# MINI_SAM_D51_010.net
KiCad netlist of a schematic drawn in EAGLE
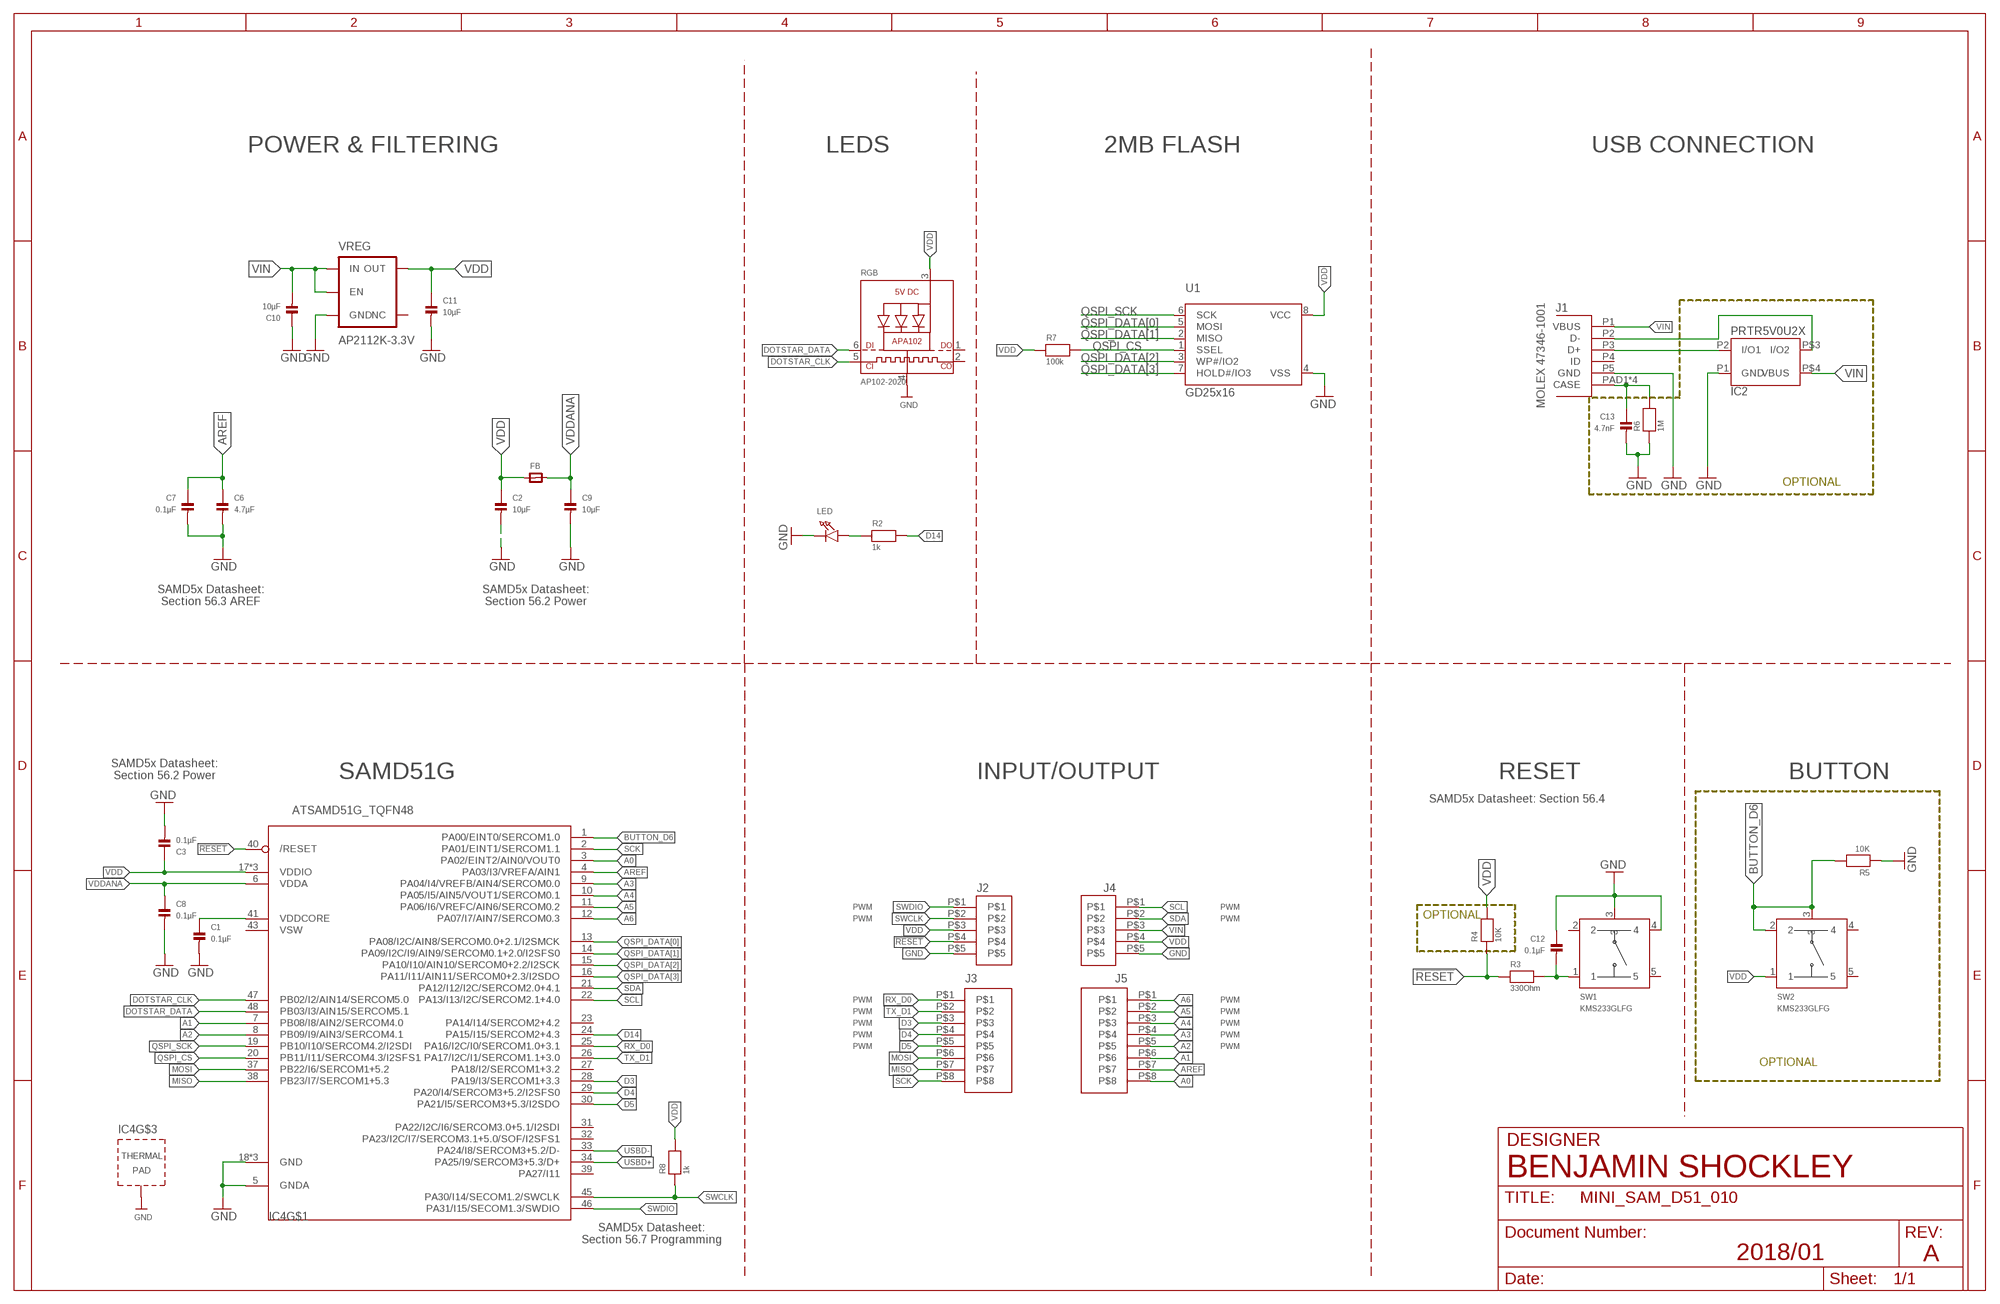
[diagram p0: schematic, sheet 1]

(export (version "E")
  (design (tool "Eeschema 10.0.6"))
  (components
    (comp (ref "C1")
      (value "0.1µF")
      (footprint "eagle-import:_0603MP")
      (libsource (lib "eagle-import") (part "CAP_CERAMIC_0603MP"))
    )
    (comp (ref "C2")
      (value "10µF")
      (footprint "eagle-import:_0603MP")
      (libsource (lib "eagle-import") (part "CAP_CERAMIC_0603MP"))
    )
    (comp (ref "C3")
      (value "0.1µF")
      (footprint "eagle-import:_0603MP")
      (libsource (lib "eagle-import") (part "CAP_CERAMIC_0603MP"))
    )
    (comp (ref "C6")
      (value "4.7µF")
      (footprint "eagle-import:_0603MP")
      (libsource (lib "eagle-import") (part "CAP_CERAMIC_0603MP"))
    )
    (comp (ref "C7")
      (value "0.1µF")
      (footprint "eagle-import:_0603MP")
      (libsource (lib "eagle-import") (part "CAP_CERAMIC_0603MP"))
    )
    (comp (ref "C8")
      (value "0.1µF")
      (footprint "eagle-import:_0603MP")
      (libsource (lib "eagle-import") (part "CAP_CERAMIC_0603MP"))
    )
    (comp (ref "C9")
      (value "10µF")
      (footprint "eagle-import:_0603MP")
      (libsource (lib "eagle-import") (part "CAP_CERAMIC_0603MP"))
    )
    (comp (ref "C10")
      (value "10µF")
      (footprint "eagle-import:_0603MP")
      (libsource (lib "eagle-import") (part "CAP_CERAMIC_0603MP"))
    )
    (comp (ref "C11")
      (value "10µF")
      (footprint "eagle-import:_0603MP")
      (libsource (lib "eagle-import") (part "CAP_CERAMIC_0603MP"))
    )
    (comp (ref "C12")
      (value "0.1µF")
      (footprint "eagle-import:_0603MP")
      (libsource (lib "eagle-import") (part "CAP_CERAMIC_0603MP"))
    )
    (comp (ref "C13")
      (value "4.7nF")
      (footprint "eagle-import:_0603MP")
      (libsource (lib "eagle-import") (part "CAP_CERAMIC_0603MP"))
    )
    (comp (ref "FB")
      (value "FERRITE_0603MP")
      (footprint "eagle-import:_0603MP")
      (libsource (lib "eagle-import") (part "FERRITE_0603MP"))
    )
    (comp (ref "IC2")
      (value "PRTR5V0U2X")
      (footprint "eagle-import:SOT143B_REFLOW")
      (libsource (lib "eagle-import") (part "PRTR5V0U2X"))
    )
    (comp (ref "IC4")
      (value "ATSAMD51G_TQFN48")
      (footprint "eagle-import:TQFN48_7MM")
      (libsource (lib "eagle-import") (part "ATSAMD51G_TQFN48"))
    )
    (comp (ref "J1")
      (value "MOLEX_47346-100147346")
      (footprint "eagle-import:MOLEX_47346-1001")
      (libsource (lib "eagle-import") (part "MOLEX_47346-100147346"))
    )
    (comp (ref "J2")
      (value "1X5_HEADER_1.27MM")
      (footprint "eagle-import:1X5_HEADER_1.27MM")
      (libsource (lib "eagle-import") (part "1X5_HEADER_1.27MM"))
    )
    (comp (ref "J3")
      (value "1X8_HEADER_1.27MM")
      (footprint "eagle-import:1X8_HEADER_1.27MM")
      (libsource (lib "eagle-import") (part "1X8_HEADER_1.27MM"))
    )
    (comp (ref "J4")
      (value "1X5_HEADER_1.27MM")
      (footprint "eagle-import:1X5_HEADER_1.27MM")
      (libsource (lib "eagle-import") (part "1X5_HEADER_1.27MM"))
    )
    (comp (ref "J5")
      (value "1X8_HEADER_1.27MM")
      (footprint "eagle-import:1X8_HEADER_1.27MM")
      (libsource (lib "eagle-import") (part "1X8_HEADER_1.27MM"))
    )
    (comp (ref "LED")
      (value "LED0805_NOOUTLINE")
      (footprint "eagle-import:CHIPLED_0805_NOOUTLINE")
      (libsource (lib "eagle-import") (part "LED0805_NOOUTLINE"))
    )
    (comp (ref "R2")
      (value "1k")
      (footprint "eagle-import:_0603MP")
      (libsource (lib "eagle-import") (part "RESISTOR_0603MP"))
    )
    (comp (ref "R3")
      (value "330Ohm")
      (footprint "eagle-import:_0603MP")
      (libsource (lib "eagle-import") (part "RESISTOR_0603MP"))
    )
    (comp (ref "R4")
      (value "10K")
      (footprint "eagle-import:_0603MP")
      (libsource (lib "eagle-import") (part "RESISTOR_0603MP"))
    )
    (comp (ref "R5")
      (value "10K")
      (footprint "eagle-import:_0603MP")
      (libsource (lib "eagle-import") (part "RESISTOR_0603MP"))
    )
    (comp (ref "R6")
      (value "1M")
      (footprint "eagle-import:_0603MP")
      (libsource (lib "eagle-import") (part "RESISTOR_0603MP"))
    )
    (comp (ref "R7")
      (value "100k")
      (footprint "eagle-import:_0603MP")
      (libsource (lib "eagle-import") (part "RESISTOR_0603MP"))
    )
    (comp (ref "R8")
      (value "1k")
      (footprint "eagle-import:_0603MP")
      (libsource (lib "eagle-import") (part "RESISTOR_0603MP"))
    )
    (comp (ref "RGB")
      (value "AP102-2020")
      (footprint "eagle-import:APA102_2020")
      (libsource (lib "eagle-import") (part "APA1022020"))
    )
    (comp (ref "SW1")
      (value "KMS233GLFG")
      (footprint "eagle-import:KMS_SWITCH")
      (libsource (lib "eagle-import") (part "KMS_SWITCHKMS"))
    )
    (comp (ref "SW2")
      (value "KMS233GLFG")
      (footprint "eagle-import:KMS_SWITCH")
      (libsource (lib "eagle-import") (part "KMS_SWITCHKMS"))
    )
    (comp (ref "U1")
      (value "GD25x16")
      (footprint "eagle-import:USON8")
      (libsource (lib "eagle-import") (part "SPIFLASH_8PINUX"))
    )
    (comp (ref "VREG")
      (value "AP2112K-3.3V")
      (footprint "eagle-import:SOT23-5")
      (libsource (lib "eagle-import") (part "V_REG_AP2112K-3.3V"))
    )
  )
  (nets
    (net (code "1") (name "/VSW") (class "Default")
      (node (ref "IC4") (pin "43") (pinfunction "VSW_43") (pintype "power_in"))
    )
    (net (code "2") (name "/~{RESET}") (class "Default")
      (node (ref "IC4") (pin "40") (pinfunction "/RESET_40") (pintype "bidirectional"))
      (node (ref "J2") (pin "P$4") (pinfunction "P$4_P$4") (pintype "bidirectional"))
      (node (ref "R3") (pin "1") (pinfunction "1_1") (pintype "passive"))
      (node (ref "R4") (pin "1") (pinfunction "1_1") (pintype "passive"))
    )
    (net (code "3") (name "A0") (class "Default")
      (node (ref "IC4") (pin "3") (pinfunction "PA02/EINT2/AIN0/VOUT0_3") (pintype "bidirectional"))
      (node (ref "J5") (pin "P$8") (pinfunction "P$8_P$8") (pintype "bidirectional"))
    )
    (net (code "4") (name "A1") (class "Default")
      (node (ref "IC4") (pin "7") (pinfunction "PB08/I8/AIN2/SERCOM4.0_7") (pintype "bidirectional"))
      (node (ref "J5") (pin "P$6") (pinfunction "P$6_P$6") (pintype "bidirectional"))
    )
    (net (code "5") (name "A2") (class "Default")
      (node (ref "IC4") (pin "8") (pinfunction "PB09/I9/AIN3/SERCOM4.1_8") (pintype "bidirectional"))
      (node (ref "J5") (pin "P$5") (pinfunction "P$5_P$5") (pintype "bidirectional"))
    )
    (net (code "6") (name "A3") (class "Default")
      (node (ref "IC4") (pin "9") (pinfunction "PA04/I4/VREFB/AIN4/SERCOM0.0_9") (pintype "bidirectional"))
      (node (ref "J5") (pin "P$4") (pinfunction "P$4_P$4") (pintype "bidirectional"))
    )
    (net (code "7") (name "A4") (class "Default")
      (node (ref "IC4") (pin "10") (pinfunction "PA05/I5/AIN5/VOUT1/SERCOM0.1_10") (pintype "bidirectional"))
      (node (ref "J5") (pin "P$3") (pinfunction "P$3_P$3") (pintype "bidirectional"))
    )
    (net (code "8") (name "A5") (class "Default")
      (node (ref "IC4") (pin "11") (pinfunction "PA06/I6/VREFC/AIN6/SERCOM0.2_11") (pintype "bidirectional"))
      (node (ref "J5") (pin "P$2") (pinfunction "P$2_P$2") (pintype "bidirectional"))
    )
    (net (code "9") (name "A6") (class "Default")
      (node (ref "IC4") (pin "12") (pinfunction "PA07/I7/AIN7/SERCOM0.3_12") (pintype "bidirectional"))
      (node (ref "J5") (pin "P$1") (pinfunction "P$1_P$1") (pintype "bidirectional"))
    )
    (net (code "10") (name "AREF") (class "Default")
      (node (ref "C6") (pin "1") (pinfunction "P$1_1") (pintype "passive"))
      (node (ref "C7") (pin "1") (pinfunction "P$1_1") (pintype "passive"))
      (node (ref "IC4") (pin "4") (pinfunction "PA03/I3/VREFA/AIN1_4") (pintype "bidirectional"))
      (node (ref "J5") (pin "P$7") (pinfunction "P$7_P$7") (pintype "bidirectional"))
    )
    (net (code "11") (name "BUTTON_D6") (class "Default")
      (node (ref "IC4") (pin "1") (pinfunction "PA00/EINT0/SERCOM1.0_1") (pintype "bidirectional"))
      (node (ref "R5") (pin "2") (pinfunction "2_2") (pintype "passive"))
      (node (ref "SW2") (pin "2") (pinfunction "2_2") (pintype "bidirectional"))
      (node (ref "SW2") (pin "3") (pinfunction "3_3") (pintype "bidirectional"))
    )
    (net (code "12") (name "D3") (class "Default")
      (node (ref "IC4") (pin "28") (pinfunction "PA19/I3/SERCOM1+3.3_28") (pintype "bidirectional"))
      (node (ref "J3") (pin "P$3") (pinfunction "P$3_P$3") (pintype "bidirectional"))
    )
    (net (code "13") (name "D4") (class "Default")
      (node (ref "IC4") (pin "29") (pinfunction "PA20/I4/SERCOM3+5.2/I2SFS0_29") (pintype "bidirectional"))
      (node (ref "J3") (pin "P$4") (pinfunction "P$4_P$4") (pintype "bidirectional"))
    )
    (net (code "14") (name "D5") (class "Default")
      (node (ref "IC4") (pin "30") (pinfunction "PA21/I5/SERCOM3+5.3/I2SDO_30") (pintype "bidirectional"))
      (node (ref "J3") (pin "P$5") (pinfunction "P$5_P$5") (pintype "bidirectional"))
    )
    (net (code "15") (name "D14") (class "Default")
      (node (ref "IC4") (pin "24") (pinfunction "PA15/I15/SERCOM2+4.3_24") (pintype "bidirectional"))
      (node (ref "R2") (pin "2") (pinfunction "2_2") (pintype "passive"))
    )
    (net (code "16") (name "DOTSTAR_CLK") (class "Default")
      (node (ref "IC4") (pin "47") (pinfunction "PB02/I2/AIN14/SERCOM5.0_47") (pintype "bidirectional"))
      (node (ref "RGB") (pin "5") (pinfunction "CKI_5") (pintype "input"))
    )
    (net (code "17") (name "DOTSTAR_DATA") (class "Default")
      (node (ref "IC4") (pin "48") (pinfunction "PB03/I3/AIN15/SERCOM5.1_48") (pintype "bidirectional"))
      (node (ref "RGB") (pin "6") (pinfunction "DI_6") (pintype "input"))
    )
    (net (code "18") (name "GND") (class "Default")
      (node (ref "C1") (pin "2") (pinfunction "P$2_2") (pintype "passive"))
      (node (ref "C10") (pin "1") (pinfunction "P$1_1") (pintype "passive"))
      (node (ref "C11") (pin "2") (pinfunction "P$2_2") (pintype "passive"))
      (node (ref "C12") (pin "1") (pinfunction "P$1_1") (pintype "passive"))
      (node (ref "C13") (pin "2") (pinfunction "P$2_2") (pintype "passive"))
      (node (ref "C2") (pin "2") (pinfunction "P$2_2") (pintype "passive"))
      (node (ref "C3") (pin "2") (pinfunction "P$2_2") (pintype "passive"))
      (node (ref "C6") (pin "2") (pinfunction "P$2_2") (pintype "passive"))
      (node (ref "C7") (pin "2") (pinfunction "P$2_2") (pintype "passive"))
      (node (ref "C8") (pin "2") (pinfunction "P$2_2") (pintype "passive"))
      (node (ref "C9") (pin "2") (pinfunction "P$2_2") (pintype "passive"))
      (node (ref "IC2") (pin "P1") (pinfunction "GND_P1") (pintype "bidirectional"))
      (node (ref "IC4") (pin "18") (pinfunction "GND_18") (pintype "power_in"))
      (node (ref "IC4") (pin "35") (pinfunction "GND_35") (pintype "power_in"))
      (node (ref "IC4") (pin "42") (pinfunction "GND_42") (pintype "power_in"))
      (node (ref "IC4") (pin "5") (pinfunction "GNDA_5") (pintype "power_in"))
      (node (ref "IC4") (pin "THERMAL") (pinfunction "TP_THERMAL") (pintype "power_in"))
      (node (ref "J1") (pin "P5") (pinfunction "GND_P5") (pintype "power_in"))
      (node (ref "J2") (pin "P$5") (pinfunction "P$5_P$5") (pintype "bidirectional"))
      (node (ref "J4") (pin "P$5") (pinfunction "P$5_P$5") (pintype "bidirectional"))
      (node (ref "LED") (pin "C") (pinfunction "C_C") (pintype "passive"))
      (node (ref "R5") (pin "1") (pinfunction "1_1") (pintype "passive"))
      (node (ref "R6") (pin "1") (pinfunction "1_1") (pintype "passive"))
      (node (ref "RGB") (pin "4") (pinfunction "GND_4") (pintype "power_in"))
      (node (ref "SW1") (pin "3") (pinfunction "3_3") (pintype "bidirectional"))
      (node (ref "SW1") (pin "4") (pinfunction "4_4") (pintype "bidirectional"))
      (node (ref "U1") (pin "4") (pinfunction "VSS_4") (pintype "bidirectional"))
      (node (ref "VREG") (pin "2") (pinfunction "GND_2") (pintype "input"))
    )
    (net (code "19") (name "MISO") (class "Default")
      (node (ref "IC4") (pin "38") (pinfunction "PB23/I7/SERCOM1+5.3_38") (pintype "bidirectional"))
      (node (ref "J3") (pin "P$7") (pinfunction "P$7_P$7") (pintype "bidirectional"))
    )
    (net (code "20") (name "MOSI") (class "Default")
      (node (ref "IC4") (pin "37") (pinfunction "PB22/I6/SERCOM1+5.2_37") (pintype "bidirectional"))
      (node (ref "J3") (pin "P$6") (pinfunction "P$6_P$6") (pintype "bidirectional"))
    )
    (net (code "21") (name "Net-(C1-P$1)") (class "Default")
      (node (ref "C1") (pin "1") (pinfunction "P$1_1") (pintype "passive"))
      (node (ref "IC4") (pin "41") (pinfunction "VDDCORE_41") (pintype "power_in"))
    )
    (net (code "22") (name "Net-(C12-P$2)") (class "Default")
      (node (ref "C12") (pin "2") (pinfunction "P$2_2") (pintype "passive"))
      (node (ref "R3") (pin "2") (pinfunction "2_2") (pintype "passive"))
      (node (ref "SW1") (pin "1") (pinfunction "1_1") (pintype "bidirectional"))
    )
    (net (code "23") (name "Net-(C13-P$1)") (class "Default")
      (node (ref "C13") (pin "1") (pinfunction "P$1_1") (pintype "passive"))
      (node (ref "J1") (pin "PAD1") (pinfunction "CASE_PAD1") (pintype "bidirectional"))
      (node (ref "J1") (pin "PAD2") (pinfunction "CASE_PAD2") (pintype "bidirectional"))
      (node (ref "J1") (pin "PAD3") (pinfunction "CASE_PAD3") (pintype "bidirectional"))
      (node (ref "J1") (pin "PAD4") (pinfunction "CASE_PAD4") (pintype "bidirectional"))
      (node (ref "R6") (pin "2") (pinfunction "2_2") (pintype "passive"))
    )
    (net (code "24") (name "Net-(LED-PadA)") (class "Default")
      (node (ref "LED") (pin "A") (pinfunction "A_A") (pintype "passive"))
      (node (ref "R2") (pin "1") (pinfunction "1_1") (pintype "passive"))
    )
    (net (code "25") (name "QSPI_CS") (class "Default")
      (node (ref "IC4") (pin "20") (pinfunction "PB11/I11/SERCOM4.3/I2SFS1_20") (pintype "bidirectional"))
      (node (ref "R7") (pin "2") (pinfunction "2_2") (pintype "passive"))
      (node (ref "U1") (pin "1") (pinfunction "SSEL_1") (pintype "bidirectional"))
    )
    (net (code "26") (name "QSPI_DATA[0]") (class "Default")
      (node (ref "IC4") (pin "13") (pinfunction "PA08/I2C/AIN8/SERCOM0.0+2.1/I2SMCK_13") (pintype "bidirectional"))
      (node (ref "U1") (pin "5") (pinfunction "MOSI_5") (pintype "bidirectional"))
    )
    (net (code "27") (name "QSPI_DATA[1]") (class "Default")
      (node (ref "IC4") (pin "14") (pinfunction "PA09/I2C/I9/AIN9/SERCOM0.1+2.0/I2SFS0_14") (pintype "bidirectional"))
      (node (ref "U1") (pin "2") (pinfunction "MISO_2") (pintype "bidirectional"))
    )
    (net (code "28") (name "QSPI_DATA[2]") (class "Default")
      (node (ref "IC4") (pin "15") (pinfunction "PA10/I10/AIN10/SERCOM0+2.2/I2SCK_15") (pintype "bidirectional"))
      (node (ref "U1") (pin "3") (pinfunction "WP#/IO2_3") (pintype "bidirectional"))
    )
    (net (code "29") (name "QSPI_DATA[3]") (class "Default")
      (node (ref "IC4") (pin "16") (pinfunction "PA11/I11/AIN11/SERCOM0+2.3/I2SDO_16") (pintype "bidirectional"))
      (node (ref "U1") (pin "7") (pinfunction "HOLD#/IO3_7") (pintype "bidirectional"))
    )
    (net (code "30") (name "QSPI_SCK") (class "Default")
      (node (ref "IC4") (pin "19") (pinfunction "PB10/I10/SERCOM4.2/I2SDI_19") (pintype "bidirectional"))
      (node (ref "U1") (pin "6") (pinfunction "SCK_6") (pintype "bidirectional"))
    )
    (net (code "31") (name "RX_D0") (class "Default")
      (node (ref "IC4") (pin "25") (pinfunction "PA16/I2C/I0/SERCOM1.0+3.1_25") (pintype "bidirectional"))
      (node (ref "J3") (pin "P$1") (pinfunction "P$1_P$1") (pintype "bidirectional"))
    )
    (net (code "32") (name "SCK") (class "Default")
      (node (ref "IC4") (pin "2") (pinfunction "PA01/EINT1/SERCOM1.1_2") (pintype "bidirectional"))
      (node (ref "J3") (pin "P$8") (pinfunction "P$8_P$8") (pintype "bidirectional"))
    )
    (net (code "33") (name "SCL") (class "Default")
      (node (ref "IC4") (pin "22") (pinfunction "PA13/I13/I2C/SERCOM2.1+4.0_22") (pintype "bidirectional"))
      (node (ref "J4") (pin "P$1") (pinfunction "P$1_P$1") (pintype "bidirectional"))
    )
    (net (code "34") (name "SDA") (class "Default")
      (node (ref "IC4") (pin "21") (pinfunction "PA12/I12/I2C/SERCOM2.0+4.1_21") (pintype "bidirectional"))
      (node (ref "J4") (pin "P$2") (pinfunction "P$2_P$2") (pintype "bidirectional"))
    )
    (net (code "35") (name "SWCLK") (class "Default")
      (node (ref "IC4") (pin "45") (pinfunction "PA30/I14/SECOM1.2/SWCLK_45") (pintype "bidirectional"))
      (node (ref "J2") (pin "P$2") (pinfunction "P$2_P$2") (pintype "bidirectional"))
      (node (ref "R8") (pin "1") (pinfunction "1_1") (pintype "passive"))
    )
    (net (code "36") (name "SWDIO") (class "Default")
      (node (ref "IC4") (pin "46") (pinfunction "PA31/I15/SECOM1.3/SWDIO_46") (pintype "bidirectional"))
      (node (ref "J2") (pin "P$1") (pinfunction "P$1_P$1") (pintype "bidirectional"))
    )
    (net (code "37") (name "TX_D1") (class "Default")
      (node (ref "IC4") (pin "26") (pinfunction "PA17/I2C/I1/SERCOM1.1+3.0_26") (pintype "bidirectional"))
      (node (ref "J3") (pin "P$2") (pinfunction "P$2_P$2") (pintype "bidirectional"))
    )
    (net (code "38") (name "USBD+") (class "Default")
      (node (ref "IC2") (pin "P2") (pinfunction "I/O1_P2") (pintype "bidirectional"))
      (node (ref "IC4") (pin "34") (pinfunction "PA25/I9/SERCOM3+5.3/D+_34") (pintype "bidirectional"))
      (node (ref "J1") (pin "P3") (pinfunction "D+_P3") (pintype "bidirectional"))
    )
    (net (code "39") (name "USBD-") (class "Default")
      (node (ref "IC2") (pin "P$3") (pinfunction "I/O2_P$3") (pintype "bidirectional"))
      (node (ref "IC4") (pin "33") (pinfunction "PA24/I8/SERCOM3+5.2/D-_33") (pintype "bidirectional"))
      (node (ref "J1") (pin "P2") (pinfunction "D-_P2") (pintype "bidirectional"))
    )
    (net (code "40") (name "VDD") (class "Default")
      (node (ref "C11") (pin "1") (pinfunction "P$1_1") (pintype "passive"))
      (node (ref "C2") (pin "1") (pinfunction "P$1_1") (pintype "passive"))
      (node (ref "C3") (pin "1") (pinfunction "P$1_1") (pintype "passive"))
      (node (ref "FB") (pin "1") (pinfunction "P$1_1") (pintype "passive"))
      (node (ref "IC4") (pin "17") (pinfunction "VDDIO_17") (pintype "power_in"))
      (node (ref "IC4") (pin "36") (pinfunction "VDDIO_36") (pintype "power_in"))
      (node (ref "IC4") (pin "44") (pinfunction "VDDIO_44") (pintype "power_in"))
      (node (ref "J2") (pin "P$3") (pinfunction "P$3_P$3") (pintype "bidirectional"))
      (node (ref "J4") (pin "P$4") (pinfunction "P$4_P$4") (pintype "bidirectional"))
      (node (ref "R4") (pin "2") (pinfunction "2_2") (pintype "passive"))
      (node (ref "R7") (pin "1") (pinfunction "1_1") (pintype "passive"))
      (node (ref "R8") (pin "2") (pinfunction "2_2") (pintype "passive"))
      (node (ref "RGB") (pin "3") (pinfunction "VDD_3") (pintype "power_in"))
      (node (ref "SW2") (pin "1") (pinfunction "1_1") (pintype "bidirectional"))
      (node (ref "U1") (pin "8") (pinfunction "VCC_8") (pintype "bidirectional"))
      (node (ref "VREG") (pin "5") (pinfunction "OUT_5") (pintype "passive"))
    )
    (net (code "41") (name "VDDANA") (class "Default")
      (node (ref "C8") (pin "1") (pinfunction "P$1_1") (pintype "passive"))
      (node (ref "C9") (pin "1") (pinfunction "P$1_1") (pintype "passive"))
      (node (ref "FB") (pin "2") (pinfunction "P$2_2") (pintype "passive"))
      (node (ref "IC4") (pin "6") (pinfunction "VDDA_6") (pintype "power_in"))
    )
    (net (code "42") (name "VIN") (class "Default")
      (node (ref "C10") (pin "2") (pinfunction "P$2_2") (pintype "passive"))
      (node (ref "IC2") (pin "P$4") (pinfunction "VBUS_P$4") (pintype "bidirectional"))
      (node (ref "J1") (pin "P1") (pinfunction "VBUS_P1") (pintype "power_in"))
      (node (ref "J4") (pin "P$3") (pinfunction "P$3_P$3") (pintype "bidirectional"))
      (node (ref "VREG") (pin "1") (pinfunction "IN_1") (pintype "input"))
      (node (ref "VREG") (pin "3") (pinfunction "EN_3") (pintype "input"))
    )
    (net (code "43") (name "unconnected-(IC4A-PA14{slash}I14{slash}SERCOM2+4.2-Pad23)") (class "Default")
      (node (ref "IC4") (pin "23") (pinfunction "PA14/I14/SERCOM2+4.2_23") (pintype "bidirectional"))
    )
    (net (code "44") (name "unconnected-(IC4A-PA18{slash}I2{slash}SERCOM1+3.2-Pad27)") (class "Default")
      (node (ref "IC4") (pin "27") (pinfunction "PA18/I2/SERCOM1+3.2_27") (pintype "bidirectional"))
    )
    (net (code "45") (name "unconnected-(IC4A-PA22{slash}I2C{slash}I6{slash}SERCOM3.0+5.1{slash}I2SDI-Pad31)") (class "Default")
      (node (ref "IC4") (pin "31") (pinfunction "PA22/I2C/I6/SERCOM3.0+5.1/I2SDI_31") (pintype "bidirectional"))
    )
    (net (code "46") (name "unconnected-(IC4A-PA23{slash}I2C{slash}I7{slash}SERCOM3.1+5.0{slash}SOF{slash}I2SFS1-Pad32)") (class "Default")
      (node (ref "IC4") (pin "32") (pinfunction "PA23/I2C/I7/SERCOM3.1+5.0/SOF/I2SFS1_32") (pintype "bidirectional"))
    )
    (net (code "47") (name "unconnected-(IC4A-PA27{slash}I11-Pad39)") (class "Default")
      (node (ref "IC4") (pin "39") (pinfunction "PA27/I11_39") (pintype "bidirectional"))
    )
    (net (code "48") (name "unconnected-(J1-ID-PadP4)") (class "Default")
      (node (ref "J1") (pin "P4") (pinfunction "ID_P4") (pintype "bidirectional"))
    )
    (net (code "49") (name "unconnected-(RGB-CKO-Pad2)") (class "Default")
      (node (ref "RGB") (pin "2") (pinfunction "CKO_2") (pintype "output"))
    )
    (net (code "50") (name "unconnected-(RGB-DO-Pad1)") (class "Default")
      (node (ref "RGB") (pin "1") (pinfunction "DO_1") (pintype "output"))
    )
    (net (code "51") (name "unconnected-(SW1-Pad2)") (class "Default")
      (node (ref "SW1") (pin "2") (pinfunction "2_2") (pintype "bidirectional"))
    )
    (net (code "52") (name "unconnected-(SW1-Pad5)") (class "Default")
      (node (ref "SW1") (pin "5") (pinfunction "5_5") (pintype "bidirectional"))
    )
    (net (code "53") (name "unconnected-(SW2-Pad4)") (class "Default")
      (node (ref "SW2") (pin "4") (pinfunction "4_4") (pintype "bidirectional"))
    )
    (net (code "54") (name "unconnected-(SW2-Pad5)") (class "Default")
      (node (ref "SW2") (pin "5") (pinfunction "5_5") (pintype "bidirectional"))
    )
    (net (code "55") (name "unconnected-(VREG-NC-Pad4)") (class "Default")
      (node (ref "VREG") (pin "4") (pinfunction "NC_4") (pintype "input"))
    )
  )
)
